# MK_II.net
KiCad netlist of a schematic drawn in EAGLE
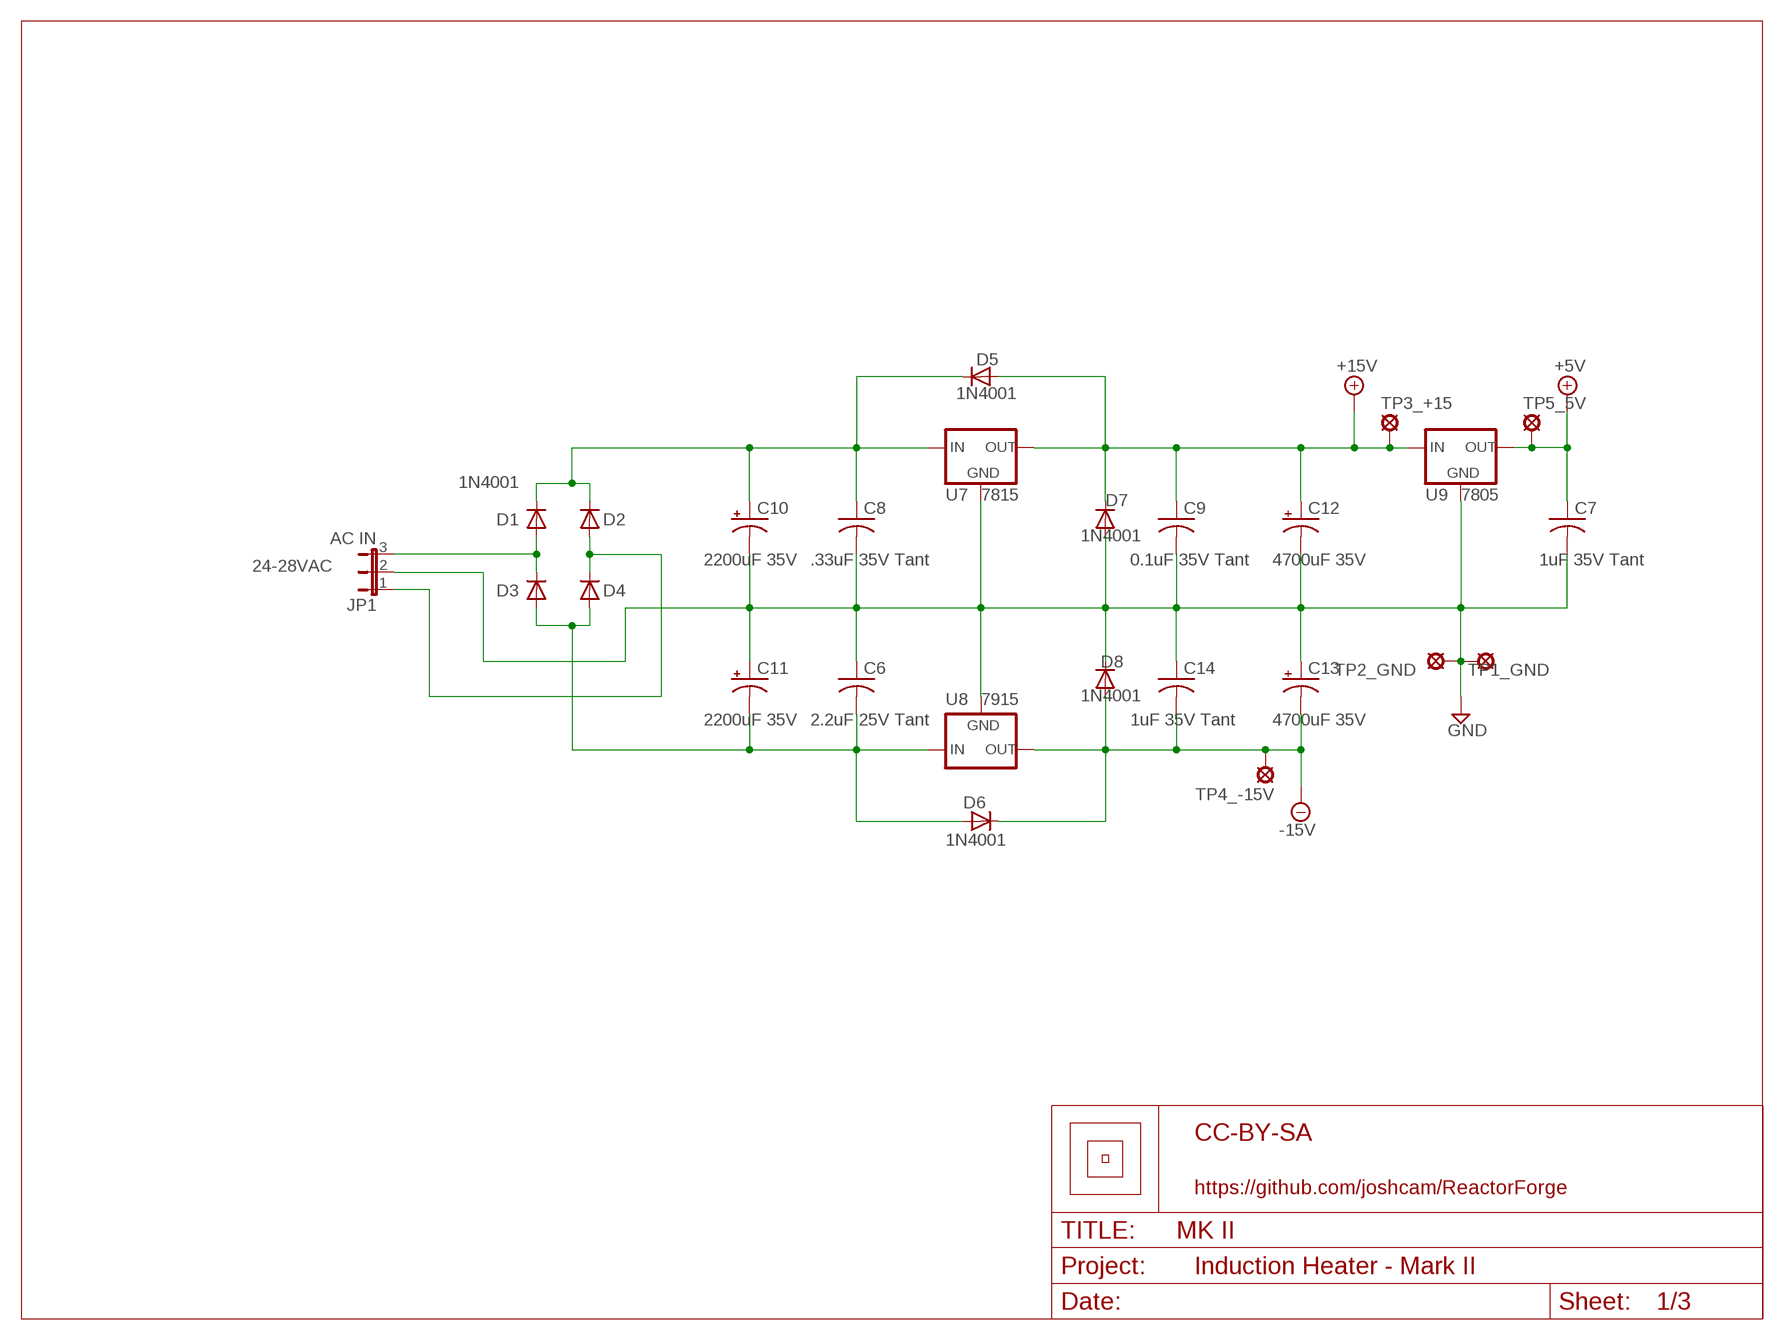
[diagram p0: schematic, sheet 1]
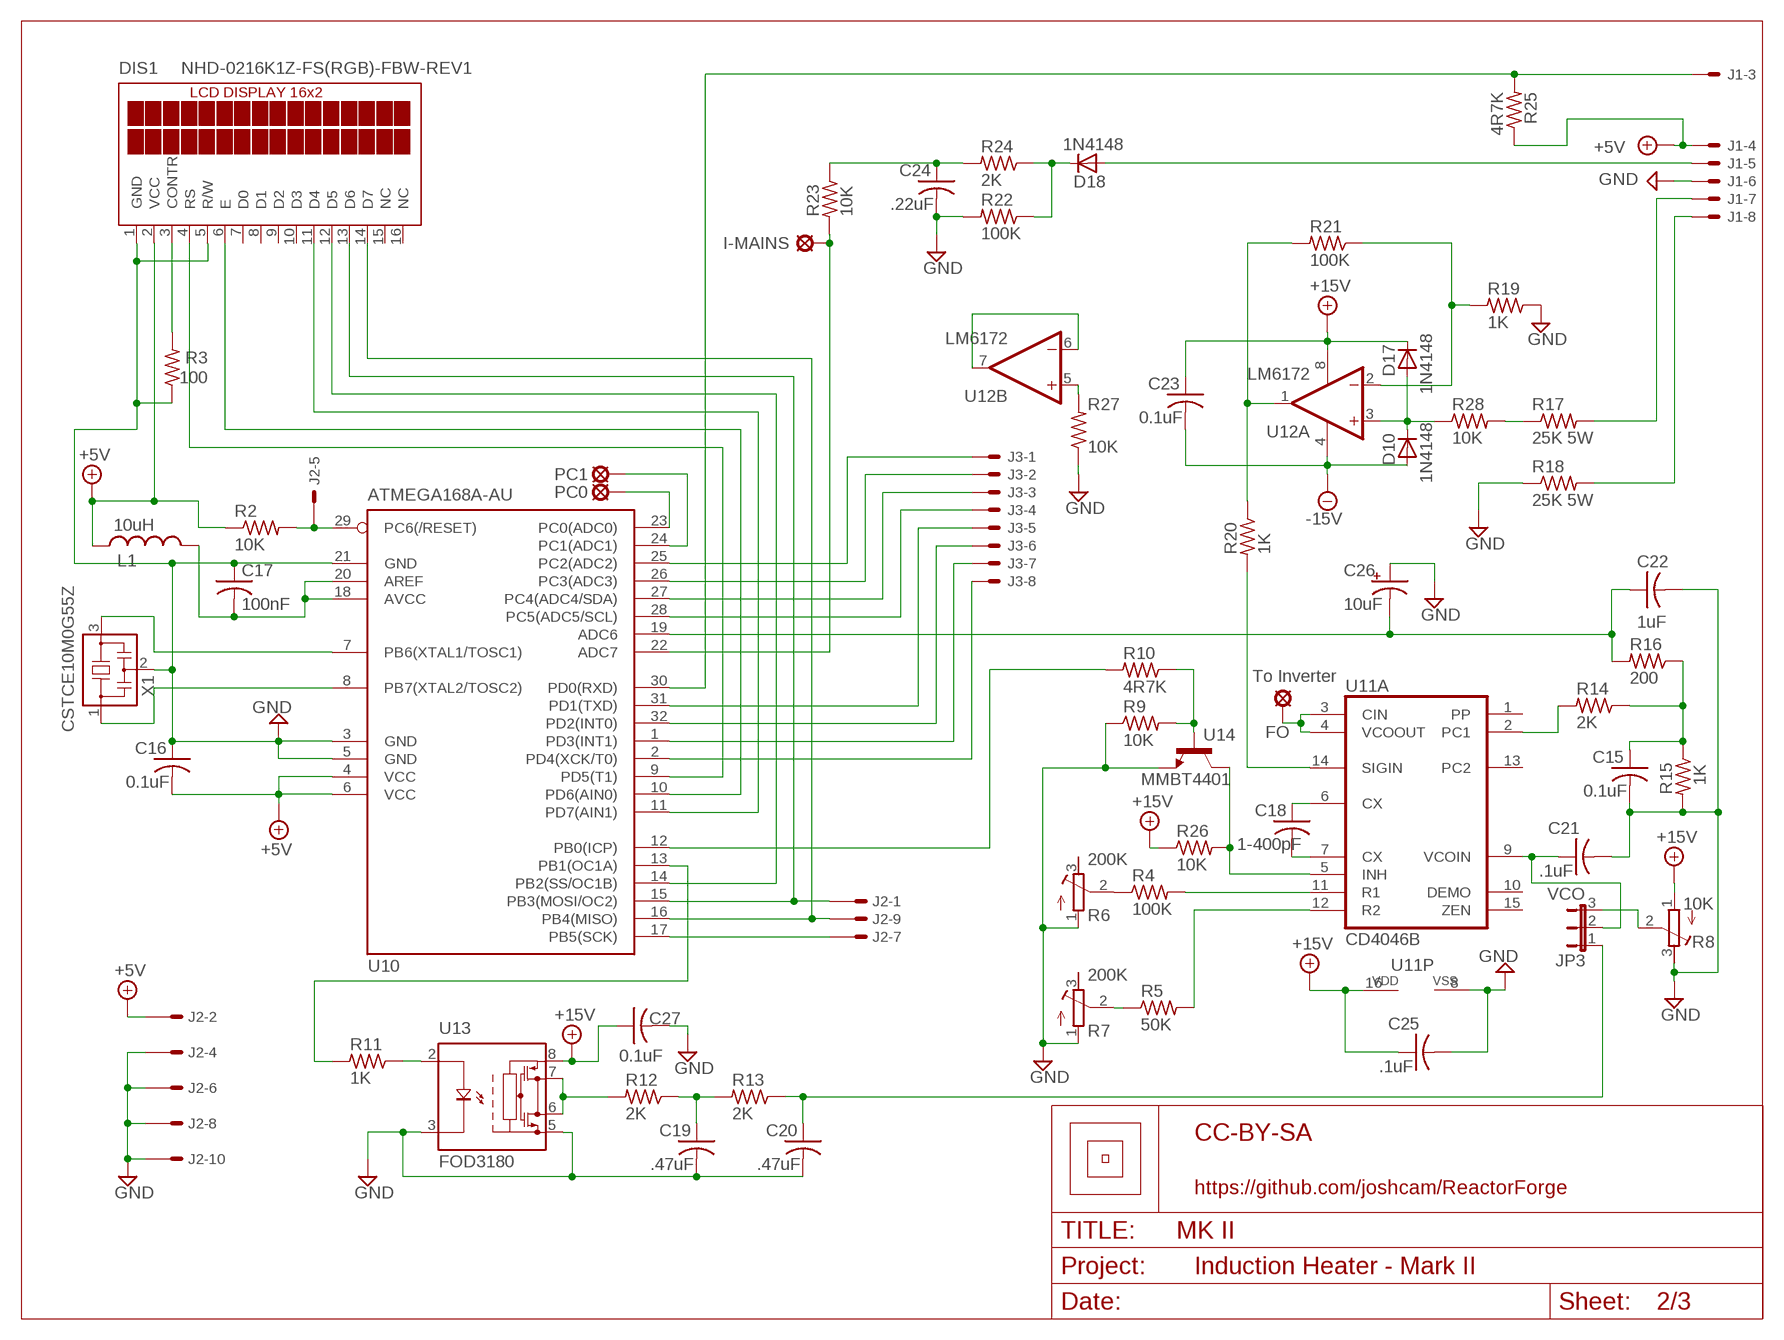
[diagram p1: schematic, sheet 2]
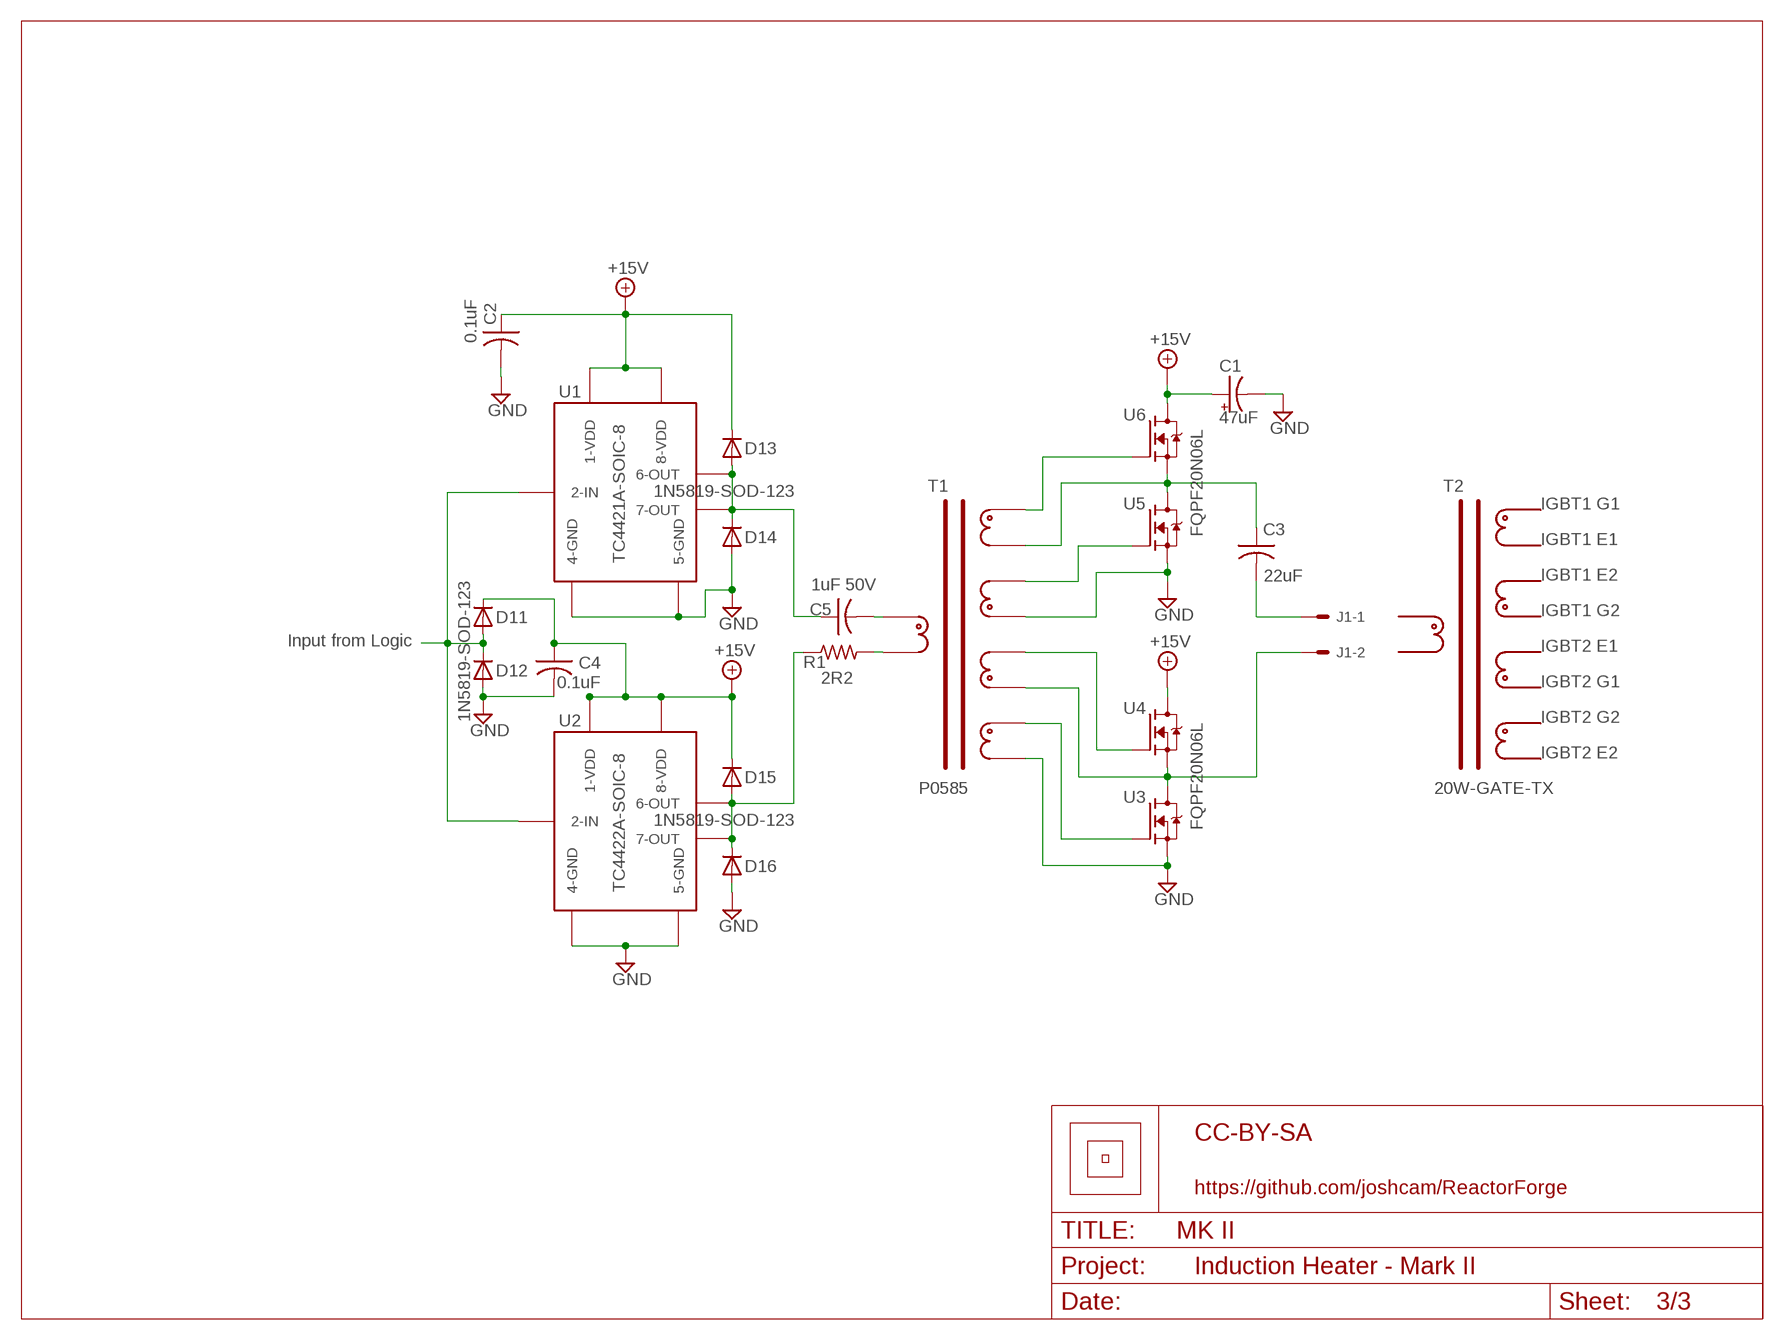
[diagram p2: schematic, sheet 3]

(export (version "E")
  (design (tool "Eeschema 10.0.6"))
  (components
    (comp (ref "C1")
      (value "47uF")
      (footprint "eagle-import:E2,5-7")
      (libsource (lib "eagle-import") (part "CPOL-USE2.5-7"))
    )
    (comp (ref "C2")
      (value "0.1uF")
      (footprint "eagle-import:C1206")
      (libsource (lib "eagle-import") (part "C-USC1206"))
    )
    (comp (ref "C3")
      (value "22uF")
      (footprint "eagle-import:C1206")
      (libsource (lib "eagle-import") (part "C-USC1206"))
    )
    (comp (ref "C4")
      (value "0.1uF")
      (footprint "eagle-import:C1206")
      (libsource (lib "eagle-import") (part "C-USC1206"))
    )
    (comp (ref "C5")
      (value "1uF 50V")
      (footprint "eagle-import:C1206")
      (libsource (lib "eagle-import") (part "C-USC1206"))
    )
    (comp (ref "D11")
      (value "1N5819-SOD-123")
      (footprint "eagle-import:SOD-123")
      (libsource (lib "eagle-import") (part "1N5819-SOD-123"))
    )
    (comp (ref "D12")
      (value "1N5819-SOD-123")
      (footprint "eagle-import:SOD-123")
      (libsource (lib "eagle-import") (part "1N5819-SOD-123"))
    )
    (comp (ref "D13")
      (value "1N5819-SOD-123")
      (footprint "eagle-import:SOD-123")
      (libsource (lib "eagle-import") (part "1N5819-SOD-123"))
    )
    (comp (ref "D14")
      (value "1N5819-SOD-123")
      (footprint "eagle-import:SOD-123")
      (libsource (lib "eagle-import") (part "1N5819-SOD-123"))
    )
    (comp (ref "D15")
      (value "1N5819-SOD-123")
      (footprint "eagle-import:SOD-123")
      (libsource (lib "eagle-import") (part "1N5819-SOD-123"))
    )
    (comp (ref "D16")
      (value "1N5819-SOD-123")
      (footprint "eagle-import:SOD-123")
      (libsource (lib "eagle-import") (part "1N5819-SOD-123"))
    )
    (comp (ref "J1")
      (value "22-23-2081")
      (footprint "eagle-import:22-23-2081")
      (fields (field (name "MF") "MOLEX"))
      (libsource (lib "eagle-import") (part "22-23-2081"))
    )
    (comp (ref "R1")
      (value "2R2")
      (footprint "eagle-import:0207_10")
      (libsource (lib "eagle-import") (part "R-US_0207/10"))
    )
    (comp (ref "T1")
      (value "P0585")
      (footprint "eagle-import:P0585")
      (libsource (lib "eagle-import") (part "P0585"))
    )
    (comp (ref "U1")
      (value "TC4421A-SOIC-8")
      (footprint "eagle-import:SOIC-8")
      (libsource (lib "eagle-import") (part "TC4421A-SOIC-8"))
    )
    (comp (ref "U2")
      (value "TC4422A-SOIC-8")
      (footprint "eagle-import:SOIC-8")
      (libsource (lib "eagle-import") (part "TC4422A-SOIC-8"))
    )
    (comp (ref "U3")
      (value "FQPF20N06L")
      (footprint "eagle-import:TO-220-V")
      (libsource (lib "eagle-import") (part "FQPF20N06L"))
    )
    (comp (ref "U4")
      (value "FQPF20N06L")
      (footprint "eagle-import:TO-220-V")
      (libsource (lib "eagle-import") (part "FQPF20N06L"))
    )
    (comp (ref "U5")
      (value "FQPF20N06L")
      (footprint "eagle-import:TO-220-V")
      (libsource (lib "eagle-import") (part "FQPF20N06L"))
    )
    (comp (ref "U6")
      (value "FQPF20N06L")
      (footprint "eagle-import:TO-220-V")
      (libsource (lib "eagle-import") (part "FQPF20N06L"))
    )
    (comp (ref "C6")
      (value "2.2uF 25V Tant")
      (footprint "eagle-import:C1206")
      (libsource (lib "eagle-import") (part "C-USC1206"))
    )
    (comp (ref "C7")
      (value "1uF 35V Tant")
      (footprint "eagle-import:C1206")
      (libsource (lib "eagle-import") (part "C-USC1206"))
    )
    (comp (ref "C8")
      (value ".33uF 35V Tant")
      (footprint "eagle-import:C1206")
      (libsource (lib "eagle-import") (part "C-USC1206"))
    )
    (comp (ref "C9")
      (value "0.1uF 35V Tant")
      (footprint "eagle-import:C1206")
      (libsource (lib "eagle-import") (part "C-USC1206"))
    )
    (comp (ref "C10")
      (value "2200uF 35V")
      (footprint "eagle-import:E7,5-18")
      (libsource (lib "eagle-import") (part "CPOL-USE7.5-18"))
    )
    (comp (ref "C11")
      (value "2200uF 35V")
      (footprint "eagle-import:E7,5-18")
      (libsource (lib "eagle-import") (part "CPOL-USE7.5-18"))
    )
    (comp (ref "C12")
      (value "4700uF 35V")
      (footprint "eagle-import:E7,5-18")
      (libsource (lib "eagle-import") (part "CPOL-USE7.5-18"))
    )
    (comp (ref "C13")
      (value "4700uF 35V")
      (footprint "eagle-import:E7,5-18")
      (libsource (lib "eagle-import") (part "CPOL-USE7.5-18"))
    )
    (comp (ref "C14")
      (value "1uF 35V Tant")
      (footprint "eagle-import:C1206")
      (libsource (lib "eagle-import") (part "C-USC1206"))
    )
    (comp (ref "D1")
      (value "1N4001")
      (footprint "eagle-import:DIODE.4-AXIAL")
      (libsource (lib "eagle-import") (part "1N4001"))
    )
    (comp (ref "D2")
      (value "1N4001")
      (footprint "eagle-import:DIODE.4-AXIAL")
      (libsource (lib "eagle-import") (part "1N4001"))
    )
    (comp (ref "D3")
      (value "1N4001")
      (footprint "eagle-import:DIODE.4-AXIAL")
      (libsource (lib "eagle-import") (part "1N4001"))
    )
    (comp (ref "D4")
      (value "1N4001")
      (footprint "eagle-import:DIODE.4-AXIAL")
      (libsource (lib "eagle-import") (part "1N4001"))
    )
    (comp (ref "D5")
      (value "1N4001")
      (footprint "eagle-import:DIODE.4-AXIAL")
      (libsource (lib "eagle-import") (part "1N4001"))
    )
    (comp (ref "D6")
      (value "1N4001")
      (footprint "eagle-import:DIODE.4-AXIAL")
      (libsource (lib "eagle-import") (part "1N4001"))
    )
    (comp (ref "D7")
      (value "1N4001")
      (footprint "eagle-import:DIODE.4-AXIAL")
      (libsource (lib "eagle-import") (part "1N4001"))
    )
    (comp (ref "D8")
      (value "1N4001")
      (footprint "eagle-import:DIODE.4-AXIAL")
      (libsource (lib "eagle-import") (part "1N4001"))
    )
    (comp (ref "JP1")
      (value "AC IN")
      (footprint "eagle-import:JP2")
      (libsource (lib "eagle-import") (part "JP2E"))
    )
    (comp (ref "TP1_GND")
      (value "SE14")
      (footprint "eagle-import:SE14")
      (libsource (lib "eagle-import") (part "SE14"))
    )
    (comp (ref "TP2_GND")
      (value "SE14")
      (footprint "eagle-import:SE14")
      (libsource (lib "eagle-import") (part "SE14"))
    )
    (comp (ref "TP3_+15")
      (value "SE14")
      (footprint "eagle-import:SE14")
      (libsource (lib "eagle-import") (part "SE14"))
    )
    (comp (ref "TP4_-15V")
      (value "SE14")
      (footprint "eagle-import:SE14")
      (libsource (lib "eagle-import") (part "SE14"))
    )
    (comp (ref "TP5_5V")
      (value "SE14")
      (footprint "eagle-import:SE14")
      (libsource (lib "eagle-import") (part "SE14"))
    )
    (comp (ref "U7")
      (value "7815")
      (footprint "eagle-import:78XXS")
      (libsource (lib "eagle-import") (part "78XXS"))
    )
    (comp (ref "U8")
      (value "7915")
      (footprint "eagle-import:79XXS")
      (libsource (lib "eagle-import") (part "79XXS"))
    )
    (comp (ref "U9")
      (value "7805")
      (footprint "eagle-import:78XXS")
      (libsource (lib "eagle-import") (part "78XXS"))
    )
    (comp (ref "C15")
      (value "0.1uF")
      (footprint "eagle-import:C1206")
      (libsource (lib "eagle-import") (part "C-USC1206"))
    )
    (comp (ref "C16")
      (value "0.1uF")
      (footprint "eagle-import:C1206")
      (libsource (lib "eagle-import") (part "C-USC1206"))
    )
    (comp (ref "C17")
      (value "100nF")
      (footprint "eagle-import:C1206")
      (libsource (lib "eagle-import") (part "C-USC1206"))
    )
    (comp (ref "C18")
      (value "1-400pF")
      (footprint "eagle-import:C1206")
      (libsource (lib "eagle-import") (part "C-USC1206"))
    )
    (comp (ref "C19")
      (value ".47uF")
      (footprint "eagle-import:C1206")
      (libsource (lib "eagle-import") (part "C-USC1206"))
    )
    (comp (ref "C20")
      (value ".47uF")
      (footprint "eagle-import:C1206")
      (libsource (lib "eagle-import") (part "C-USC1206"))
    )
    (comp (ref "C21")
      (value ".1uF")
      (footprint "eagle-import:C1206")
      (libsource (lib "eagle-import") (part "C-USC1206"))
    )
    (comp (ref "C22")
      (value "1uF")
      (footprint "eagle-import:C1206")
      (libsource (lib "eagle-import") (part "C-USC1206"))
    )
    (comp (ref "C23")
      (value "0.1uF")
      (footprint "eagle-import:C1206")
      (libsource (lib "eagle-import") (part "C-USC1206"))
    )
    (comp (ref "C24")
      (value ".22uF")
      (footprint "eagle-import:C1206")
      (libsource (lib "eagle-import") (part "C-USC1206"))
    )
    (comp (ref "C25")
      (value ".1uF")
      (footprint "eagle-import:C1206")
      (libsource (lib "eagle-import") (part "C-USC1206"))
    )
    (comp (ref "C26")
      (value "10uF")
      (footprint "eagle-import:E2,5-7")
      (libsource (lib "eagle-import") (part "CPOL-USE2.5-7"))
    )
    (comp (ref "C27")
      (value "0.1uF")
      (footprint "eagle-import:C1206")
      (libsource (lib "eagle-import") (part "C-USC1206"))
    )
    (comp (ref "D10")
      (value "1N4148")
      (footprint "eagle-import:SOD-123")
      (libsource (lib "eagle-import") (part "1N4148"))
    )
    (comp (ref "D17")
      (value "1N4148")
      (footprint "eagle-import:SOD-123")
      (libsource (lib "eagle-import") (part "1N4148"))
    )
    (comp (ref "D18")
      (value "1N4148")
      (footprint "eagle-import:SOD-123")
      (libsource (lib "eagle-import") (part "1N4148"))
    )
    (comp (ref "DIS1")
      (value "NHD-0216K1Z-FS(RGB)-FBW-REV1")
      (footprint "eagle-import:TUXGR_16X2_R2")
      (libsource (lib "eagle-import") (part "TUXGR_16X2_R2"))
    )
    (comp (ref "FO")
      (value "SE14")
      (footprint "eagle-import:SE14")
      (libsource (lib "eagle-import") (part "SE14"))
    )
    (comp (ref "I-MAINS")
      (value "SE14")
      (footprint "eagle-import:SE14")
      (libsource (lib "eagle-import") (part "SE14"))
    )
    (comp (ref "J2")
      (value "057-010-1")
      (footprint "eagle-import:057-010-1")
      (libsource (lib "eagle-import") (part "057-010-1"))
    )
    (comp (ref "J3")
      (value "22-23-2081")
      (footprint "eagle-import:22-23-2081")
      (fields (field (name "MF") "MOLEX"))
      (libsource (lib "eagle-import") (part "22-23-2081"))
    )
    (comp (ref "JP3")
      (value "VCO")
      (footprint "eagle-import:JP2")
      (libsource (lib "eagle-import") (part "JP2E"))
    )
    (comp (ref "L1")
      (value "10uH")
      (footprint "eagle-import:L2012C")
      (libsource (lib "eagle-import") (part "L-USL2012C"))
    )
    (comp (ref "PC0")
      (value "SE14")
      (footprint "eagle-import:SE14")
      (libsource (lib "eagle-import") (part "SE14"))
    )
    (comp (ref "PC1")
      (value "SE14")
      (footprint "eagle-import:SE14")
      (libsource (lib "eagle-import") (part "SE14"))
    )
    (comp (ref "R2")
      (value "10K")
      (footprint "eagle-import:M1206")
      (libsource (lib "eagle-import") (part "resistor_R-US_M1206"))
    )
    (comp (ref "R3")
      (value "100")
      (footprint "eagle-import:M1206")
      (libsource (lib "eagle-import") (part "resistor_R-US_M1206"))
    )
    (comp (ref "R4")
      (value "100K")
      (footprint "eagle-import:M1206")
      (libsource (lib "eagle-import") (part "resistor_R-US_M1206"))
    )
    (comp (ref "R5")
      (value "50K")
      (footprint "eagle-import:M1206")
      (libsource (lib "eagle-import") (part "resistor_R-US_M1206"))
    )
    (comp (ref "R6")
      (value "200K")
      (footprint "eagle-import:RTRIM4G_J")
      (libsource (lib "eagle-import") (part "R-TRIMM4G/J"))
    )
    (comp (ref "R7")
      (value "200K")
      (footprint "eagle-import:RTRIM4G_J")
      (libsource (lib "eagle-import") (part "R-TRIMM4G/J"))
    )
    (comp (ref "R8")
      (value "10K")
      (footprint "eagle-import:RTRIM4G_J")
      (libsource (lib "eagle-import") (part "R-TRIMM4G/J"))
    )
    (comp (ref "R9")
      (value "10K")
      (footprint "eagle-import:M1206")
      (libsource (lib "eagle-import") (part "resistor_R-US_M1206"))
    )
    (comp (ref "R10")
      (value "4R7K")
      (footprint "eagle-import:M1206")
      (libsource (lib "eagle-import") (part "resistor_R-US_M1206"))
    )
    (comp (ref "R11")
      (value "1K")
      (footprint "eagle-import:M1206")
      (libsource (lib "eagle-import") (part "resistor_R-US_M1206"))
    )
    (comp (ref "R12")
      (value "2K")
      (footprint "eagle-import:M1206")
      (libsource (lib "eagle-import") (part "resistor_R-US_M1206"))
    )
    (comp (ref "R13")
      (value "2K")
      (footprint "eagle-import:M1206")
      (libsource (lib "eagle-import") (part "resistor_R-US_M1206"))
    )
    (comp (ref "R14")
      (value "2K")
      (footprint "eagle-import:M1206")
      (libsource (lib "eagle-import") (part "resistor_R-US_M1206"))
    )
    (comp (ref "R15")
      (value "1K")
      (footprint "eagle-import:M1206")
      (libsource (lib "eagle-import") (part "resistor_R-US_M1206"))
    )
    (comp (ref "R16")
      (value "200")
      (footprint "eagle-import:M1206")
      (libsource (lib "eagle-import") (part "resistor_R-US_M1206"))
    )
    (comp (ref "R17")
      (value "25K 5W")
      (footprint "eagle-import:0617_22")
      (libsource (lib "eagle-import") (part "resistor_R-US_0617/22"))
    )
    (comp (ref "R18")
      (value "25K 5W")
      (footprint "eagle-import:0617_22")
      (libsource (lib "eagle-import") (part "resistor_R-US_0617/22"))
    )
    (comp (ref "R19")
      (value "1K")
      (footprint "eagle-import:M1206")
      (libsource (lib "eagle-import") (part "resistor_R-US_M1206"))
    )
    (comp (ref "R20")
      (value "1K")
      (footprint "eagle-import:M1206")
      (libsource (lib "eagle-import") (part "resistor_R-US_M1206"))
    )
    (comp (ref "R21")
      (value "100K")
      (footprint "eagle-import:M1206")
      (libsource (lib "eagle-import") (part "resistor_R-US_M1206"))
    )
    (comp (ref "R22")
      (value "100K")
      (footprint "eagle-import:M1206")
      (libsource (lib "eagle-import") (part "resistor_R-US_M1206"))
    )
    (comp (ref "R23")
      (value "10K")
      (footprint "eagle-import:M1206")
      (libsource (lib "eagle-import") (part "resistor_R-US_M1206"))
    )
    (comp (ref "R24")
      (value "2K")
      (footprint "eagle-import:M1206")
      (libsource (lib "eagle-import") (part "resistor_R-US_M1206"))
    )
    (comp (ref "R25")
      (value "4R7K")
      (footprint "eagle-import:M1206")
      (libsource (lib "eagle-import") (part "resistor_R-US_M1206"))
    )
    (comp (ref "R26")
      (value "10K")
      (footprint "eagle-import:M1206")
      (libsource (lib "eagle-import") (part "resistor_R-US_M1206"))
    )
    (comp (ref "R27")
      (value "10K")
      (footprint "eagle-import:M1206")
      (libsource (lib "eagle-import") (part "resistor_R-US_M1206"))
    )
    (comp (ref "R28")
      (value "10K")
      (footprint "eagle-import:M1206")
      (libsource (lib "eagle-import") (part "resistor_R-US_M1206"))
    )
    (comp (ref "U10")
      (value "ATMEGA168A-AU")
      (footprint "eagle-import:TQFP32-08")
      (fields (field (name "MPN") "ATMEGA8-16AU"))
      (libsource (lib "eagle-import") (part "MEGA8-AI"))
    )
    (comp (ref "U11")
      (value "CD4046B")
      (footprint "eagle-import:SO16")
      (libsource (lib "eagle-import") (part "4046D"))
    )
    (comp (ref "U12")
      (value "LM6172")
      (footprint "eagle-import:SO08")
      (libsource (lib "eagle-import") (part "LM358D"))
    )
    (comp (ref "U13")
      (value "FOD3180")
      (footprint "eagle-import:SO08")
      (libsource (lib "eagle-import") (part "FOD3180"))
    )
    (comp (ref "U14")
      (value "MMBT4401")
      (footprint "eagle-import:SOT23")
      (libsource (lib "eagle-import") (part "MMBT4401"))
    )
    (comp (ref "X1")
      (value "CSTCE10M0G55Z")
      (footprint "eagle-import:3-SMD")
      (libsource (lib "eagle-import") (part "CSTCE10M0G55Z"))
    )
  )
  (nets
    (net (code "1") (name "+5V") (class "Default")
      (node (ref "C16") (pin "2") (pinfunction "2_2") (pintype "passive"))
      (node (ref "C7") (pin "1") (pinfunction "1_1") (pintype "passive"))
      (node (ref "DIS1") (pin "2") (pinfunction "VCC_2") (pintype "power_in"))
      (node (ref "J1") (pin "4") (pinfunction "S_4") (pintype "passive"))
      (node (ref "J2") (pin "2") (pinfunction "S_2") (pintype "passive"))
      (node (ref "L1") (pin "1") (pinfunction "1_1") (pintype "passive"))
      (node (ref "R2") (pin "1") (pinfunction "1_1") (pintype "passive"))
      (node (ref "R25") (pin "1") (pinfunction "1_1") (pintype "passive"))
      (node (ref "TP5_5V") (pin "MP") (pinfunction "MP_MP") (pintype "passive"))
      (node (ref "U10") (pin "4") (pinfunction "VCC_4") (pintype "power_in"))
      (node (ref "U10") (pin "6") (pinfunction "VCC_6") (pintype "power_in"))
      (node (ref "U9") (pin "OUT") (pinfunction "OUT_OUT") (pintype "passive"))
    )
    (net (code "2") (name "+15V") (class "Default")
      (node (ref "C1") (pin "+") (pinfunction "+_+") (pintype "passive"))
      (node (ref "C12") (pin "+") (pinfunction "+_+") (pintype "passive"))
      (node (ref "C2") (pin "1") (pinfunction "1_1") (pintype "passive"))
      (node (ref "C23") (pin "1") (pinfunction "1_1") (pintype "passive"))
      (node (ref "C25") (pin "1") (pinfunction "1_1") (pintype "passive"))
      (node (ref "C27") (pin "1") (pinfunction "1_1") (pintype "passive"))
      (node (ref "C4") (pin "1") (pinfunction "1_1") (pintype "passive"))
      (node (ref "C9") (pin "1") (pinfunction "1_1") (pintype "passive"))
      (node (ref "D11") (pin "C") (pinfunction "C_C") (pintype "passive"))
      (node (ref "D13") (pin "C") (pinfunction "C_C") (pintype "passive"))
      (node (ref "D15") (pin "C") (pinfunction "C_C") (pintype "passive"))
      (node (ref "D17") (pin "C") (pinfunction "C_C") (pintype "passive"))
      (node (ref "D5") (pin "A") (pinfunction "A_A") (pintype "passive"))
      (node (ref "D7") (pin "C") (pinfunction "C_C") (pintype "passive"))
      (node (ref "R26") (pin "1") (pinfunction "1_1") (pintype "passive"))
      (node (ref "R8") (pin "1") (pinfunction "E_1") (pintype "passive"))
      (node (ref "TP3_+15") (pin "MP") (pinfunction "MP_MP") (pintype "passive"))
      (node (ref "U1") (pin "P$1") (pinfunction "1-VDD_P$1") (pintype "power_in"))
      (node (ref "U1") (pin "P$8") (pinfunction "8-VDD_P$8") (pintype "power_in"))
      (node (ref "U11") (pin "16") (pinfunction "VDD_16") (pintype "power_in"))
      (node (ref "U12") (pin "8") (pinfunction "V+_8") (pintype "power_in"))
      (node (ref "U13") (pin "8") (pinfunction "P$8_8") (pintype "passive"))
      (node (ref "U2") (pin "P$1") (pinfunction "1-VDD_P$1") (pintype "power_in"))
      (node (ref "U2") (pin "P$8") (pinfunction "8-VDD_P$8") (pintype "power_in"))
      (node (ref "U4") (pin "2") (pinfunction "D_2") (pintype "passive"))
      (node (ref "U6") (pin "2") (pinfunction "D_2") (pintype "passive"))
      (node (ref "U7") (pin "OUT") (pinfunction "OUT_OUT") (pintype "passive"))
      (node (ref "U9") (pin "IN") (pinfunction "IN_IN") (pintype "input"))
    )
    (net (code "3") (name "-15V") (class "Default")
      (node (ref "C13") (pin "-") (pinfunction "-_-") (pintype "passive"))
      (node (ref "C14") (pin "2") (pinfunction "2_2") (pintype "passive"))
      (node (ref "C23") (pin "2") (pinfunction "2_2") (pintype "passive"))
      (node (ref "D10") (pin "A") (pinfunction "A_A") (pintype "passive"))
      (node (ref "D6") (pin "C") (pinfunction "C_C") (pintype "passive"))
      (node (ref "D8") (pin "A") (pinfunction "A_A") (pintype "passive"))
      (node (ref "TP4_-15V") (pin "MP") (pinfunction "MP_MP") (pintype "passive"))
      (node (ref "U12") (pin "4") (pinfunction "V-_4") (pintype "power_in"))
      (node (ref "U8") (pin "OUT") (pinfunction "OUT_OUT") (pintype "passive"))
    )
    (net (code "4") (name "FO") (class "Default")
      (node (ref "D11") (pin "A") (pinfunction "A_A") (pintype "passive"))
      (node (ref "D12") (pin "C") (pinfunction "C_C") (pintype "passive"))
      (node (ref "FO") (pin "MP") (pinfunction "MP_MP") (pintype "passive"))
      (node (ref "U1") (pin "P$2") (pinfunction "2-IN_P$2") (pintype "bidirectional"))
      (node (ref "U11") (pin "3") (pinfunction "CIN_3") (pintype "input"))
      (node (ref "U11") (pin "4") (pinfunction "VCOOUT_4") (pintype "output"))
      (node (ref "U2") (pin "P$2") (pinfunction "2-IN_P$2") (pintype "bidirectional"))
    )
    (net (code "5") (name "GND") (class "Default")
      (node (ref "C1") (pin "-") (pinfunction "-_-") (pintype "passive"))
      (node (ref "C10") (pin "-") (pinfunction "-_-") (pintype "passive"))
      (node (ref "C11") (pin "+") (pinfunction "+_+") (pintype "passive"))
      (node (ref "C12") (pin "-") (pinfunction "-_-") (pintype "passive"))
      (node (ref "C13") (pin "+") (pinfunction "+_+") (pintype "passive"))
      (node (ref "C14") (pin "1") (pinfunction "1_1") (pintype "passive"))
      (node (ref "C15") (pin "2") (pinfunction "2_2") (pintype "passive"))
      (node (ref "C16") (pin "1") (pinfunction "1_1") (pintype "passive"))
      (node (ref "C17") (pin "1") (pinfunction "1_1") (pintype "passive"))
      (node (ref "C19") (pin "2") (pinfunction "2_2") (pintype "passive"))
      (node (ref "C2") (pin "2") (pinfunction "2_2") (pintype "passive"))
      (node (ref "C20") (pin "2") (pinfunction "2_2") (pintype "passive"))
      (node (ref "C21") (pin "2") (pinfunction "2_2") (pintype "passive"))
      (node (ref "C22") (pin "2") (pinfunction "2_2") (pintype "passive"))
      (node (ref "C24") (pin "2") (pinfunction "2_2") (pintype "passive"))
      (node (ref "C25") (pin "2") (pinfunction "2_2") (pintype "passive"))
      (node (ref "C26") (pin "+") (pinfunction "+_+") (pintype "passive"))
      (node (ref "C27") (pin "2") (pinfunction "2_2") (pintype "passive"))
      (node (ref "C4") (pin "2") (pinfunction "2_2") (pintype "passive"))
      (node (ref "C6") (pin "1") (pinfunction "1_1") (pintype "passive"))
      (node (ref "C7") (pin "2") (pinfunction "2_2") (pintype "passive"))
      (node (ref "C8") (pin "2") (pinfunction "2_2") (pintype "passive"))
      (node (ref "C9") (pin "2") (pinfunction "2_2") (pintype "passive"))
      (node (ref "D12") (pin "A") (pinfunction "A_A") (pintype "passive"))
      (node (ref "D14") (pin "A") (pinfunction "A_A") (pintype "passive"))
      (node (ref "D16") (pin "A") (pinfunction "A_A") (pintype "passive"))
      (node (ref "D7") (pin "A") (pinfunction "A_A") (pintype "passive"))
      (node (ref "D8") (pin "C") (pinfunction "C_C") (pintype "passive"))
      (node (ref "DIS1") (pin "1") (pinfunction "GND_1") (pintype "power_in"))
      (node (ref "DIS1") (pin "5") (pinfunction "R/W_5") (pintype "input"))
      (node (ref "J1") (pin "6") (pinfunction "S_6") (pintype "passive"))
      (node (ref "J2") (pin "10") (pinfunction "S_10") (pintype "passive"))
      (node (ref "J2") (pin "4") (pinfunction "S_4") (pintype "passive"))
      (node (ref "J2") (pin "6") (pinfunction "S_6") (pintype "passive"))
      (node (ref "J2") (pin "8") (pinfunction "S_8") (pintype "passive"))
      (node (ref "JP1") (pin "2") (pinfunction "2_2") (pintype "passive"))
      (node (ref "R15") (pin "2") (pinfunction "2_2") (pintype "passive"))
      (node (ref "R18") (pin "1") (pinfunction "1_1") (pintype "passive"))
      (node (ref "R19") (pin "1") (pinfunction "1_1") (pintype "passive"))
      (node (ref "R22") (pin "2") (pinfunction "2_2") (pintype "passive"))
      (node (ref "R27") (pin "1") (pinfunction "1_1") (pintype "passive"))
      (node (ref "R3") (pin "1") (pinfunction "1_1") (pintype "passive"))
      (node (ref "R6") (pin "1") (pinfunction "E_1") (pintype "passive"))
      (node (ref "R7") (pin "1") (pinfunction "E_1") (pintype "passive"))
      (node (ref "R8") (pin "3") (pinfunction "A_3") (pintype "passive"))
      (node (ref "R9") (pin "1") (pinfunction "1_1") (pintype "passive"))
      (node (ref "T1") (pin "P$4") (pinfunction "P$4_P$4") (pintype "bidirectional"))
      (node (ref "T1") (pin "P$6") (pinfunction "P$6_P$6") (pintype "bidirectional"))
      (node (ref "TP1_GND") (pin "MP") (pinfunction "MP_MP") (pintype "passive"))
      (node (ref "TP2_GND") (pin "MP") (pinfunction "MP_MP") (pintype "passive"))
      (node (ref "U1") (pin "P$4") (pinfunction "4-GND_P$4") (pintype "power_in"))
      (node (ref "U1") (pin "P$5") (pinfunction "5-GND_P$5") (pintype "power_in"))
      (node (ref "U10") (pin "21") (pinfunction "GND_21") (pintype "power_in"))
      (node (ref "U10") (pin "3") (pinfunction "GND_3") (pintype "power_in"))
      (node (ref "U10") (pin "5") (pinfunction "GND_5") (pintype "power_in"))
      (node (ref "U11") (pin "8") (pinfunction "VSS_8") (pintype "power_in"))
      (node (ref "U13") (pin "3") (pinfunction "P$3_3") (pintype "bidirectional"))
      (node (ref "U13") (pin "5") (pinfunction "P$5_5") (pintype "passive"))
      (node (ref "U14") (pin "2") (pinfunction "E_2") (pintype "passive"))
      (node (ref "U2") (pin "P$4") (pinfunction "4-GND_P$4") (pintype "power_in"))
      (node (ref "U2") (pin "P$5") (pinfunction "5-GND_P$5") (pintype "power_in"))
      (node (ref "U3") (pin "3") (pinfunction "S_3") (pintype "passive"))
      (node (ref "U5") (pin "3") (pinfunction "S_3") (pintype "passive"))
      (node (ref "U7") (pin "GND") (pinfunction "GND_GND") (pintype "input"))
      (node (ref "U8") (pin "GND") (pinfunction "GND_GND") (pintype "input"))
      (node (ref "U9") (pin "GND") (pinfunction "GND_GND") (pintype "input"))
      (node (ref "X1") (pin "2") (pinfunction "2_2") (pintype "passive"))
    )
    (net (code "6") (name "Net-(C5-Pad2)") (class "Default")
      (node (ref "C5") (pin "2") (pinfunction "2_2") (pintype "passive"))
      (node (ref "T1") (pin "P$1") (pinfunction "P$1_P$1") (pintype "bidirectional"))
    )
    (net (code "7") (name "Net-(C10-Pad+)") (class "Default")
      (node (ref "C10") (pin "+") (pinfunction "+_+") (pintype "passive"))
      (node (ref "C8") (pin "1") (pinfunction "1_1") (pintype "passive"))
      (node (ref "D1") (pin "C") (pinfunction "C_C") (pintype "passive"))
      (node (ref "D2") (pin "C") (pinfunction "C_C") (pintype "passive"))
      (node (ref "D5") (pin "C") (pinfunction "C_C") (pintype "passive"))
      (node (ref "U7") (pin "IN") (pinfunction "IN_IN") (pintype "input"))
    )
    (net (code "8") (name "Net-(C11-Pad-)") (class "Default")
      (node (ref "C11") (pin "-") (pinfunction "-_-") (pintype "passive"))
      (node (ref "C6") (pin "2") (pinfunction "2_2") (pintype "passive"))
      (node (ref "D3") (pin "A") (pinfunction "A_A") (pintype "passive"))
      (node (ref "D4") (pin "A") (pinfunction "A_A") (pintype "passive"))
      (node (ref "D6") (pin "A") (pinfunction "A_A") (pintype "passive"))
      (node (ref "U8") (pin "IN") (pinfunction "IN_IN") (pintype "input"))
    )
    (net (code "9") (name "Net-(C15-Pad1)") (class "Default")
      (node (ref "C15") (pin "1") (pinfunction "1_1") (pintype "passive"))
      (node (ref "R14") (pin "1") (pinfunction "1_1") (pintype "passive"))
      (node (ref "R15") (pin "1") (pinfunction "1_1") (pintype "passive"))
      (node (ref "R16") (pin "1") (pinfunction "1_1") (pintype "passive"))
    )
    (net (code "10") (name "Net-(C18-Pad1)") (class "Default")
      (node (ref "C18") (pin "1") (pinfunction "1_1") (pintype "passive"))
      (node (ref "U11") (pin "6") (pinfunction "CX_6") (pintype "input"))
    )
    (net (code "11") (name "Net-(C18-Pad2)") (class "Default")
      (node (ref "C18") (pin "2") (pinfunction "2_2") (pintype "passive"))
      (node (ref "U11") (pin "7") (pinfunction "CX_7") (pintype "input"))
    )
    (net (code "12") (name "Net-(C19-Pad1)") (class "Default")
      (node (ref "C19") (pin "1") (pinfunction "1_1") (pintype "passive"))
      (node (ref "R12") (pin "1") (pinfunction "1_1") (pintype "passive"))
      (node (ref "R13") (pin "2") (pinfunction "2_2") (pintype "passive"))
    )
    (net (code "13") (name "Net-(C20-Pad1)") (class "Default")
      (node (ref "C20") (pin "1") (pinfunction "1_1") (pintype "passive"))
      (node (ref "JP3") (pin "1") (pinfunction "1_1") (pintype "passive"))
      (node (ref "R13") (pin "1") (pinfunction "1_1") (pintype "passive"))
    )
    (net (code "14") (name "Net-(C24-Pad1)") (class "Default")
      (node (ref "C24") (pin "1") (pinfunction "1_1") (pintype "passive"))
      (node (ref "R23") (pin "1") (pinfunction "1_1") (pintype "passive"))
      (node (ref "R24") (pin "2") (pinfunction "2_2") (pintype "passive"))
    )
    (net (code "15") (name "Net-(D1-PadA)") (class "Default")
      (node (ref "D1") (pin "A") (pinfunction "A_A") (pintype "passive"))
      (node (ref "D3") (pin "C") (pinfunction "C_C") (pintype "passive"))
      (node (ref "JP1") (pin "3") (pinfunction "3_3") (pintype "passive"))
    )
    (net (code "16") (name "Net-(D2-PadA)") (class "Default")
      (node (ref "D2") (pin "A") (pinfunction "A_A") (pintype "passive"))
      (node (ref "D4") (pin "C") (pinfunction "C_C") (pintype "passive"))
      (node (ref "JP1") (pin "1") (pinfunction "1_1") (pintype "passive"))
    )
    (net (code "17") (name "Net-(D18-PadC)") (class "Default")
      (node (ref "D18") (pin "C") (pinfunction "C_C") (pintype "passive"))
      (node (ref "R22") (pin "1") (pinfunction "1_1") (pintype "passive"))
      (node (ref "R24") (pin "1") (pinfunction "1_1") (pintype "passive"))
    )
    (net (code "18") (name "Net-(DIS1-CONTR)") (class "Default")
      (node (ref "DIS1") (pin "3") (pinfunction "CONTR_3") (pintype "input"))
      (node (ref "R3") (pin "2") (pinfunction "2_2") (pintype "passive"))
    )
    (net (code "19") (name "Net-(DIS1-D4)") (class "Default")
      (node (ref "DIS1") (pin "11") (pinfunction "D4_11") (pintype "input"))
      (node (ref "U10") (pin "11") (pinfunction "PD7(AIN1)_11") (pintype "bidirectional"))
    )
    (net (code "20") (name "Net-(DIS1-D5)") (class "Default")
      (node (ref "DIS1") (pin "12") (pinfunction "D5_12") (pintype "input"))
      (node (ref "U10") (pin "14") (pinfunction "PB2(SS/OC1B)_14") (pintype "bidirectional"))
    )
    (net (code "21") (name "Net-(DIS1-D6)") (class "Default")
      (node (ref "DIS1") (pin "13") (pinfunction "D6_13") (pintype "input"))
      (node (ref "J2") (pin "1") (pinfunction "S_1") (pintype "passive"))
      (node (ref "U10") (pin "15") (pinfunction "PB3(MOSI/OC2)_15") (pintype "bidirectional"))
    )
    (net (code "22") (name "Net-(DIS1-D7)") (class "Default")
      (node (ref "DIS1") (pin "14") (pinfunction "D7_14") (pintype "input"))
      (node (ref "J2") (pin "9") (pinfunction "S_9") (pintype "passive"))
      (node (ref "U10") (pin "16") (pinfunction "PB4(MISO)_16") (pintype "bidirectional"))
    )
    (net (code "23") (name "Net-(DIS1-E)") (class "Default")
      (node (ref "DIS1") (pin "6") (pinfunction "E_6") (pintype "input"))
      (node (ref "U10") (pin "10") (pinfunction "PD6(AIN0)_10") (pintype "bidirectional"))
    )
    (net (code "24") (name "Net-(DIS1-RS)") (class "Default")
      (node (ref "DIS1") (pin "4") (pinfunction "RS_4") (pintype "input"))
      (node (ref "U10") (pin "9") (pinfunction "PD5(T1)_9") (pintype "bidirectional"))
    )
    (net (code "25") (name "Net-(J1A-S)") (class "Default")
      (node (ref "C3") (pin "2") (pinfunction "2_2") (pintype "passive"))
      (node (ref "J1") (pin "1") (pinfunction "S_1") (pintype "passive"))
    )
    (net (code "26") (name "Net-(J1B-S)") (class "Default")
      (node (ref "J1") (pin "2") (pinfunction "S_2") (pintype "passive"))
      (node (ref "T1") (pin "P$9") (pinfunction "P$9_P$9") (pintype "bidirectional"))
      (node (ref "U3") (pin "2") (pinfunction "D_2") (pintype "passive"))
      (node (ref "U4") (pin "3") (pinfunction "S_3") (pintype "passive"))
    )
    (net (code "27") (name "Net-(J1C-S)") (class "Default")
      (node (ref "J1") (pin "3") (pinfunction "S_3") (pintype "passive"))
      (node (ref "R25") (pin "2") (pinfunction "2_2") (pintype "passive"))
      (node (ref "U10") (pin "30") (pinfunction "PD0(RXD)_30") (pintype "bidirectional"))
    )
    (net (code "28") (name "Net-(J1E-S)") (class "Default")
      (node (ref "D18") (pin "A") (pinfunction "A_A") (pintype "passive"))
      (node (ref "J1") (pin "5") (pinfunction "S_5") (pintype "passive"))
    )
    (net (code "29") (name "Net-(J1G-S)") (class "Default")
      (node (ref "J1") (pin "7") (pinfunction "S_7") (pintype "passive"))
      (node (ref "R17") (pin "2") (pinfunction "2_2") (pintype "passive"))
    )
    (net (code "30") (name "Net-(J1H-S)") (class "Default")
      (node (ref "J1") (pin "8") (pinfunction "S_8") (pintype "passive"))
      (node (ref "R18") (pin "2") (pinfunction "2_2") (pintype "passive"))
    )
    (net (code "31") (name "Net-(J2F-S)") (class "Default")
      (node (ref "J2") (pin "5") (pinfunction "S_5") (pintype "passive"))
      (node (ref "R2") (pin "2") (pinfunction "2_2") (pintype "passive"))
      (node (ref "U10") (pin "29") (pinfunction "PC6(/RESET)_29") (pintype "bidirectional"))
    )
    (net (code "32") (name "Net-(J2H-S)") (class "Default")
      (node (ref "J2") (pin "7") (pinfunction "S_7") (pintype "passive"))
      (node (ref "U10") (pin "17") (pinfunction "PB5(SCK)_17") (pintype "bidirectional"))
    )
    (net (code "33") (name "Net-(J3A-S)") (class "Default")
      (node (ref "J3") (pin "1") (pinfunction "S_1") (pintype "passive"))
      (node (ref "U10") (pin "25") (pinfunction "PC2(ADC2)_25") (pintype "bidirectional"))
    )
    (net (code "34") (name "Net-(J3B-S)") (class "Default")
      (node (ref "J3") (pin "2") (pinfunction "S_2") (pintype "passive"))
      (node (ref "U10") (pin "26") (pinfunction "PC3(ADC3)_26") (pintype "bidirectional"))
    )
    (net (code "35") (name "Net-(J3C-S)") (class "Default")
      (node (ref "J3") (pin "3") (pinfunction "S_3") (pintype "passive"))
      (node (ref "U10") (pin "27") (pinfunction "PC4(ADC4/SDA)_27") (pintype "bidirectional"))
    )
    (net (code "36") (name "Net-(J3D-S)") (class "Default")
      (node (ref "J3") (pin "4") (pinfunction "S_4") (pintype "passive"))
      (node (ref "U10") (pin "28") (pinfunction "PC5(ADC5/SCL)_28") (pintype "bidirectional"))
    )
    (net (code "37") (name "Net-(J3E-S)") (class "Default")
      (node (ref "J3") (pin "5") (pinfunction "S_5") (pintype "passive"))
      (node (ref "U10") (pin "31") (pinfunction "PD1(TXD)_31") (pintype "bidirectional"))
    )
    (net (code "38") (name "Net-(J3F-S)") (class "Default")
      (node (ref "J3") (pin "6") (pinfunction "S_6") (pintype "passive"))
      (node (ref "U10") (pin "32") (pinfunction "PD2(INT0)_32") (pintype "bidirectional"))
    )
    (net (code "39") (name "Net-(J3G-S)") (class "Default")
      (node (ref "J3") (pin "7") (pinfunction "S_7") (pintype "passive"))
      (node (ref "U10") (pin "1") (pinfunction "PD3(INT1)_1") (pintype "bidirectional"))
    )
    (net (code "40") (name "Net-(J3H-S)") (class "Default")
      (node (ref "J3") (pin "8") (pinfunction "S_8") (pintype "passive"))
      (node (ref "U10") (pin "2") (pinfunction "PD4(XCK/T0)_2") (pintype "bidirectional"))
    )
    (net (code "41") (name "Net-(R1-Pad2)") (class "Default")
      (node (ref "R1") (pin "2") (pinfunction "2_2") (pintype "passive"))
      (node (ref "T1") (pin "P$10") (pinfunction "P$10_P$10") (pintype "bidirectional"))
    )
    (net (code "42") (name "Net-(R6-S)") (class "Default")
      (node (ref "R4") (pin "1") (pinfunction "1_1") (pintype "passive"))
      (node (ref "R6") (pin "2") (pinfunction "S_2") (pintype "passive"))
    )
    (net (code "43") (name "Net-(R7-S)") (class "Default")
      (node (ref "R5") (pin "1") (pinfunction "1_1") (pintype "passive"))
      (node (ref "R7") (pin "2") (pinfunction "S_2") (pintype "passive"))
    )
    (net (code "44") (name "Net-(R8-S)") (class "Default")
      (node (ref "JP3") (pin "3") (pinfunction "3_3") (pintype "passive"))
      (node (ref "R8") (pin "2") (pinfunction "S_2") (pintype "passive"))
    )
    (net (code "45") (name "Net-(R17-Pad1)") (class "Default")
      (node (ref "R17") (pin "1") (pinfunction "1_1") (pintype "passive"))
      (node (ref "R28") (pin "2") (pinfunction "2_2") (pintype "passive"))
    )
    (net (code "46") (name "Net-(U1-6-OUT)") (class "Default")
      (node (ref "C5") (pin "1") (pinfunction "1_1") (pintype "passive"))
      (node (ref "D13") (pin "A") (pinfunction "A_A") (pintype "passive"))
      (node (ref "D14") (pin "C") (pinfunction "C_C") (pintype "passive"))
      (node (ref "U1") (pin "P$6") (pinfunction "6-OUT_P$6") (pintype "bidirectional"))
      (node (ref "U1") (pin "P$7") (pinfunction "7-OUT_P$7") (pintype "bidirectional"))
    )
    (net (code "47") (name "Net-(U2-6-OUT)") (class "Default")
      (node (ref "D15") (pin "A") (pinfunction "A_A") (pintype "passive"))
      (node (ref "D16") (pin "C") (pinfunction "C_C") (pintype "passive"))
      (node (ref "R1") (pin "1") (pinfunction "1_1") (pintype "passive"))
      (node (ref "U2") (pin "P$6") (pinfunction "6-OUT_P$6") (pintype "bidirectional"))
      (node (ref "U2") (pin "P$7") (pinfunction "7-OUT_P$7") (pintype "bidirectional"))
    )
    (net (code "48") (name "Net-(U3-G)") (class "Default")
      (node (ref "T1") (pin "P$7") (pinfunction "P$7_P$7") (pintype "bidirectional"))
      (node (ref "U3") (pin "1") (pinfunction "G_1") (pintype "passive"))
    )
    (net (code "49") (name "Net-(U4-G)") (class "Default")
      (node (ref "T1") (pin "P$8") (pinfunction "P$8_P$8") (pintype "bidirectional"))
      (node (ref "U4") (pin "1") (pinfunction "G_1") (pintype "passive"))
    )
    (net (code "50") (name "Net-(U5-D)") (class "Default")
      (node (ref "C3") (pin "1") (pinfunction "1_1") (pintype "passive"))
      (node (ref "T1") (pin "P$3") (pinfunction "P$3_P$3") (pintype "bidirectional"))
      (node (ref "U5") (pin "2") (pinfunction "D_2") (pintype "passive"))
      (node (ref "U6") (pin "3") (pinfunction "S_3") (pintype "passive"))
    )
    (net (code "51") (name "Net-(U5-G)") (class "Default")
      (node (ref "T1") (pin "P$5") (pinfunction "P$5_P$5") (pintype "bidirectional"))
      (node (ref "U5") (pin "1") (pinfunction "G_1") (pintype "passive"))
    )
    (net (code "52") (name "Net-(U6-G)") (class "Default")
      (node (ref "T1") (pin "P$2") (pinfunction "P$2_P$2") (pintype "bidirectional"))
      (node (ref "U6") (pin "1") (pinfunction "G_1") (pintype "passive"))
    )
    (net (code "53") (name "Net-(U10-ADC6)") (class "Default")
      (node (ref "C22") (pin "1") (pinfunction "1_1") (pintype "passive"))
      (node (ref "C26") (pin "-") (pinfunction "-_-") (pintype "passive"))
      (node (ref "R16") (pin "2") (pinfunction "2_2") (pintype "passive"))
      (node (ref "U10") (pin "19") (pinfunction "ADC6_19") (pintype "bidirectional"))
    )
    (net (code "54") (name "Net-(U10-ADC7)") (class "Default")
      (node (ref "I-MAINS") (pin "MP") (pinfunction "MP_MP") (pintype "passive"))
      (node (ref "R23") (pin "2") (pinfunction "2_2") (pintype "passive"))
      (node (ref "U10") (pin "22") (pinfunction "ADC7_22") (pintype "bidirectional"))
    )
    (net (code "55") (name "Net-(U10-AREF)") (class "Default")
      (node (ref "C17") (pin "2") (pinfunction "2_2") (pintype "passive"))
      (node (ref "L1") (pin "2") (pinfunction "2_2") (pintype "passive"))
      (node (ref "U10") (pin "18") (pinfunction "AVCC_18") (pintype "power_in"))
      (node (ref "U10") (pin "20") (pinfunction "AREF_20") (pintype "passive"))
    )
    (net (code "56") (name "Net-(U10-PB0(ICP))") (class "Default")
      (node (ref "R10") (pin "2") (pinfunction "2_2") (pintype "passive"))
      (node (ref "U10") (pin "12") (pinfunction "PB0(ICP)_12") (pintype "bidirectional"))
    )
    (net (code "57") (name "Net-(U10-PB1(OC1A))") (class "Default")
      (node (ref "R11") (pin "2") (pinfunction "2_2") (pintype "passive"))
      (node (ref "U10") (pin "13") (pinfunction "PB1(OC1A)_13") (pintype "bidirectional"))
    )
    (net (code "58") (name "Net-(U10-PB6(XTAL1{slash}TOSC1))") (class "Default")
      (node (ref "U10") (pin "7") (pinfunction "PB6(XTAL1/TOSC1)_7") (pintype "bidirectional"))
      (node (ref "X1") (pin "3") (pinfunction "3_3") (pintype "passive"))
    )
    (net (code "59") (name "Net-(U10-PB7(XTAL2{slash}TOSC2))") (class "Default")
      (node (ref "U10") (pin "8") (pinfunction "PB7(XTAL2/TOSC2)_8") (pintype "bidirectional"))
      (node (ref "X1") (pin "1") (pinfunction "1_1") (pintype "passive"))
    )
    (net (code "60") (name "Net-(U10-PC0(ADC0))") (class "Default")
      (node (ref "PC0") (pin "MP") (pinfunction "MP_MP") (pintype "passive"))
      (node (ref "U10") (pin "23") (pinfunction "PC0(ADC0)_23") (pintype "bidirectional"))
    )
    (net (code "61") (name "Net-(U10-PC1(ADC1))") (class "Default")
      (node (ref "PC1") (pin "MP") (pinfunction "MP_MP") (pintype "passive"))
      (node (ref "U10") (pin "24") (pinfunction "PC1(ADC1)_24") (pintype "bidirectional"))
    )
    (net (code "62") (name "Net-(U11A-INH)") (class "Default")
      (node (ref "R26") (pin "2") (pinfunction "2_2") (pintype "passive"))
      (node (ref "U11") (pin "5") (pinfunction "INH_5") (pintype "input"))
      (node (ref "U14") (pin "3") (pinfunction "C_3") (pintype "passive"))
    )
    (net (code "63") (name "Net-(U11A-PC1)") (class "Default")
      (node (ref "R14") (pin "2") (pinfunction "2_2") (pintype "passive"))
      (node (ref "U11") (pin "2") (pinfunction "PC1_2") (pintype "output"))
    )
    (net (code "64") (name "Net-(U11A-R1)") (class "Default")
      (node (ref "R4") (pin "2") (pinfunction "2_2") (pintype "passive"))
      (node (ref "U11") (pin "11") (pinfunction "R1_11") (pintype "input"))
    )
    (net (code "65") (name "Net-(U11A-R2)") (class "Default")
      (node (ref "R5") (pin "2") (pinfunction "2_2") (pintype "passive"))
      (node (ref "U11") (pin "12") (pinfunction "R2_12") (pintype "input"))
    )
    (net (code "66") (name "Net-(U11A-SIGIN)") (class "Default")
      (node (ref "R20") (pin "2") (pinfunction "2_2") (pintype "passive"))
      (node (ref "U11") (pin "14") (pinfunction "SIGIN_14") (pintype "input"))
    )
    (net (code "67") (name "Net-(U11A-VCOIN)") (class "Default")
      (node (ref "C21") (pin "1") (pinfunction "1_1") (pintype "passive"))
      (node (ref "JP3") (pin "2") (pinfunction "2_2") (pintype "passive"))
      (node (ref "U11") (pin "9") (pinfunction "VCOIN_9") (pintype "input"))
    )
    (net (code "68") (name "Net-(U12A-+IN)") (class "Default")
      (node (ref "D10") (pin "C") (pinfunction "C_C") (pintype "passive"))
      (node (ref "D17") (pin "A") (pinfunction "A_A") (pintype "passive"))
      (node (ref "R28") (pin "1") (pinfunction "1_1") (pintype "passive"))
      (node (ref "U12") (pin "3") (pinfunction "+IN_3") (pintype "input"))
    )
    (net (code "69") (name "Net-(U12A--IN)") (class "Default")
      (node (ref "R19") (pin "2") (pinfunction "2_2") (pintype "passive"))
      (node (ref "R21") (pin "1") (pinfunction "1_1") (pintype "passive"))
      (node (ref "U12") (pin "2") (pinfunction "-IN_2") (pintype "input"))
    )
    (net (code "70") (name "Net-(U12A-OUT)") (class "Default")
      (node (ref "R20") (pin "1") (pinfunction "1_1") (pintype "passive"))
      (node (ref "R21") (pin "2") (pinfunction "2_2") (pintype "passive"))
      (node (ref "U12") (pin "1") (pinfunction "OUT_1") (pintype "output"))
    )
    (net (code "71") (name "Net-(U12B-+IN)") (class "Default")
      (node (ref "R27") (pin "2") (pinfunction "2_2") (pintype "passive"))
      (node (ref "U12") (pin "5") (pinfunction "+IN_5") (pintype "input"))
    )
    (net (code "72") (name "Net-(U12B--IN)") (class "Default")
      (node (ref "U12") (pin "6") (pinfunction "-IN_6") (pintype "input"))
      (node (ref "U12") (pin "7") (pinfunction "OUT_7") (pintype "output"))
    )
    (net (code "73") (name "Net-(U13-P$2)") (class "Default")
      (node (ref "R11") (pin "1") (pinfunction "1_1") (pintype "passive"))
      (node (ref "U13") (pin "2") (pinfunction "P$2_2") (pintype "bidirectional"))
    )
    (net (code "74") (name "Net-(U13-P$6)") (class "Default")
      (node (ref "R12") (pin "2") (pinfunction "2_2") (pintype "passive"))
      (node (ref "U13") (pin "6") (pinfunction "P$6_6") (pintype "passive"))
      (node (ref "U13") (pin "7") (pinfunction "P$7_7") (pintype "passive"))
    )
    (net (code "75") (name "Net-(U14-B)") (class "Default")
      (node (ref "R10") (pin "1") (pinfunction "1_1") (pintype "passive"))
      (node (ref "R9") (pin "2") (pinfunction "2_2") (pintype "passive"))
      (node (ref "U14") (pin "1") (pinfunction "B_1") (pintype "passive"))
    )
    (net (code "76") (name "unconnected-(DIS1-D0-Pad7)") (class "Default")
      (node (ref "DIS1") (pin "7") (pinfunction "D0_7") (pintype "input"))
    )
    (net (code "77") (name "unconnected-(DIS1-D1-Pad8)") (class "Default")
      (node (ref "DIS1") (pin "8") (pinfunction "D1_8") (pintype "input"))
    )
    (net (code "78") (name "unconnected-(DIS1-D2-Pad9)") (class "Default")
      (node (ref "DIS1") (pin "9") (pinfunction "D2_9") (pintype "input"))
    )
    (net (code "79") (name "unconnected-(DIS1-D3-Pad10)") (class "Default")
      (node (ref "DIS1") (pin "10") (pinfunction "D3_10") (pintype "input"))
    )
    (net (code "80") (name "unconnected-(DIS1-NC-Pad15)") (class "Default")
      (node (ref "DIS1") (pin "15") (pinfunction "NC_15") (pintype "no_connect"))
    )
    (net (code "81") (name "unconnected-(DIS1-NC-Pad16)") (class "Default")
      (node (ref "DIS1") (pin "16") (pinfunction "NC_16") (pintype "no_connect"))
    )
    (net (code "82") (name "unconnected-(R6-A-Pad3)") (class "Default")
      (node (ref "R6") (pin "3") (pinfunction "A_3") (pintype "passive"))
    )
    (net (code "83") (name "unconnected-(R7-A-Pad3)") (class "Default")
      (node (ref "R7") (pin "3") (pinfunction "A_3") (pintype "passive"))
    )
    (net (code "84") (name "unconnected-(U11A-DEMO-Pad10)") (class "Default")
      (node (ref "U11") (pin "10") (pinfunction "DEMO_10") (pintype "output"))
    )
    (net (code "85") (name "unconnected-(U11A-PC2-Pad13)") (class "Default")
      (node (ref "U11") (pin "13") (pinfunction "PC2_13") (pintype "output"))
    )
    (net (code "86") (name "unconnected-(U11A-PP-Pad1)") (class "Default")
      (node (ref "U11") (pin "1") (pinfunction "PP_1") (pintype "output"))
    )
    (net (code "87") (name "unconnected-(U11A-ZEN-Pad15)") (class "Default")
      (node (ref "U11") (pin "15") (pinfunction "ZEN_15") (pintype "input"))
    )
  )
)
